# RiskChemi_Sensors_V2_04M2.net
KiCad netlist of a schematic drawn in Altium Designer
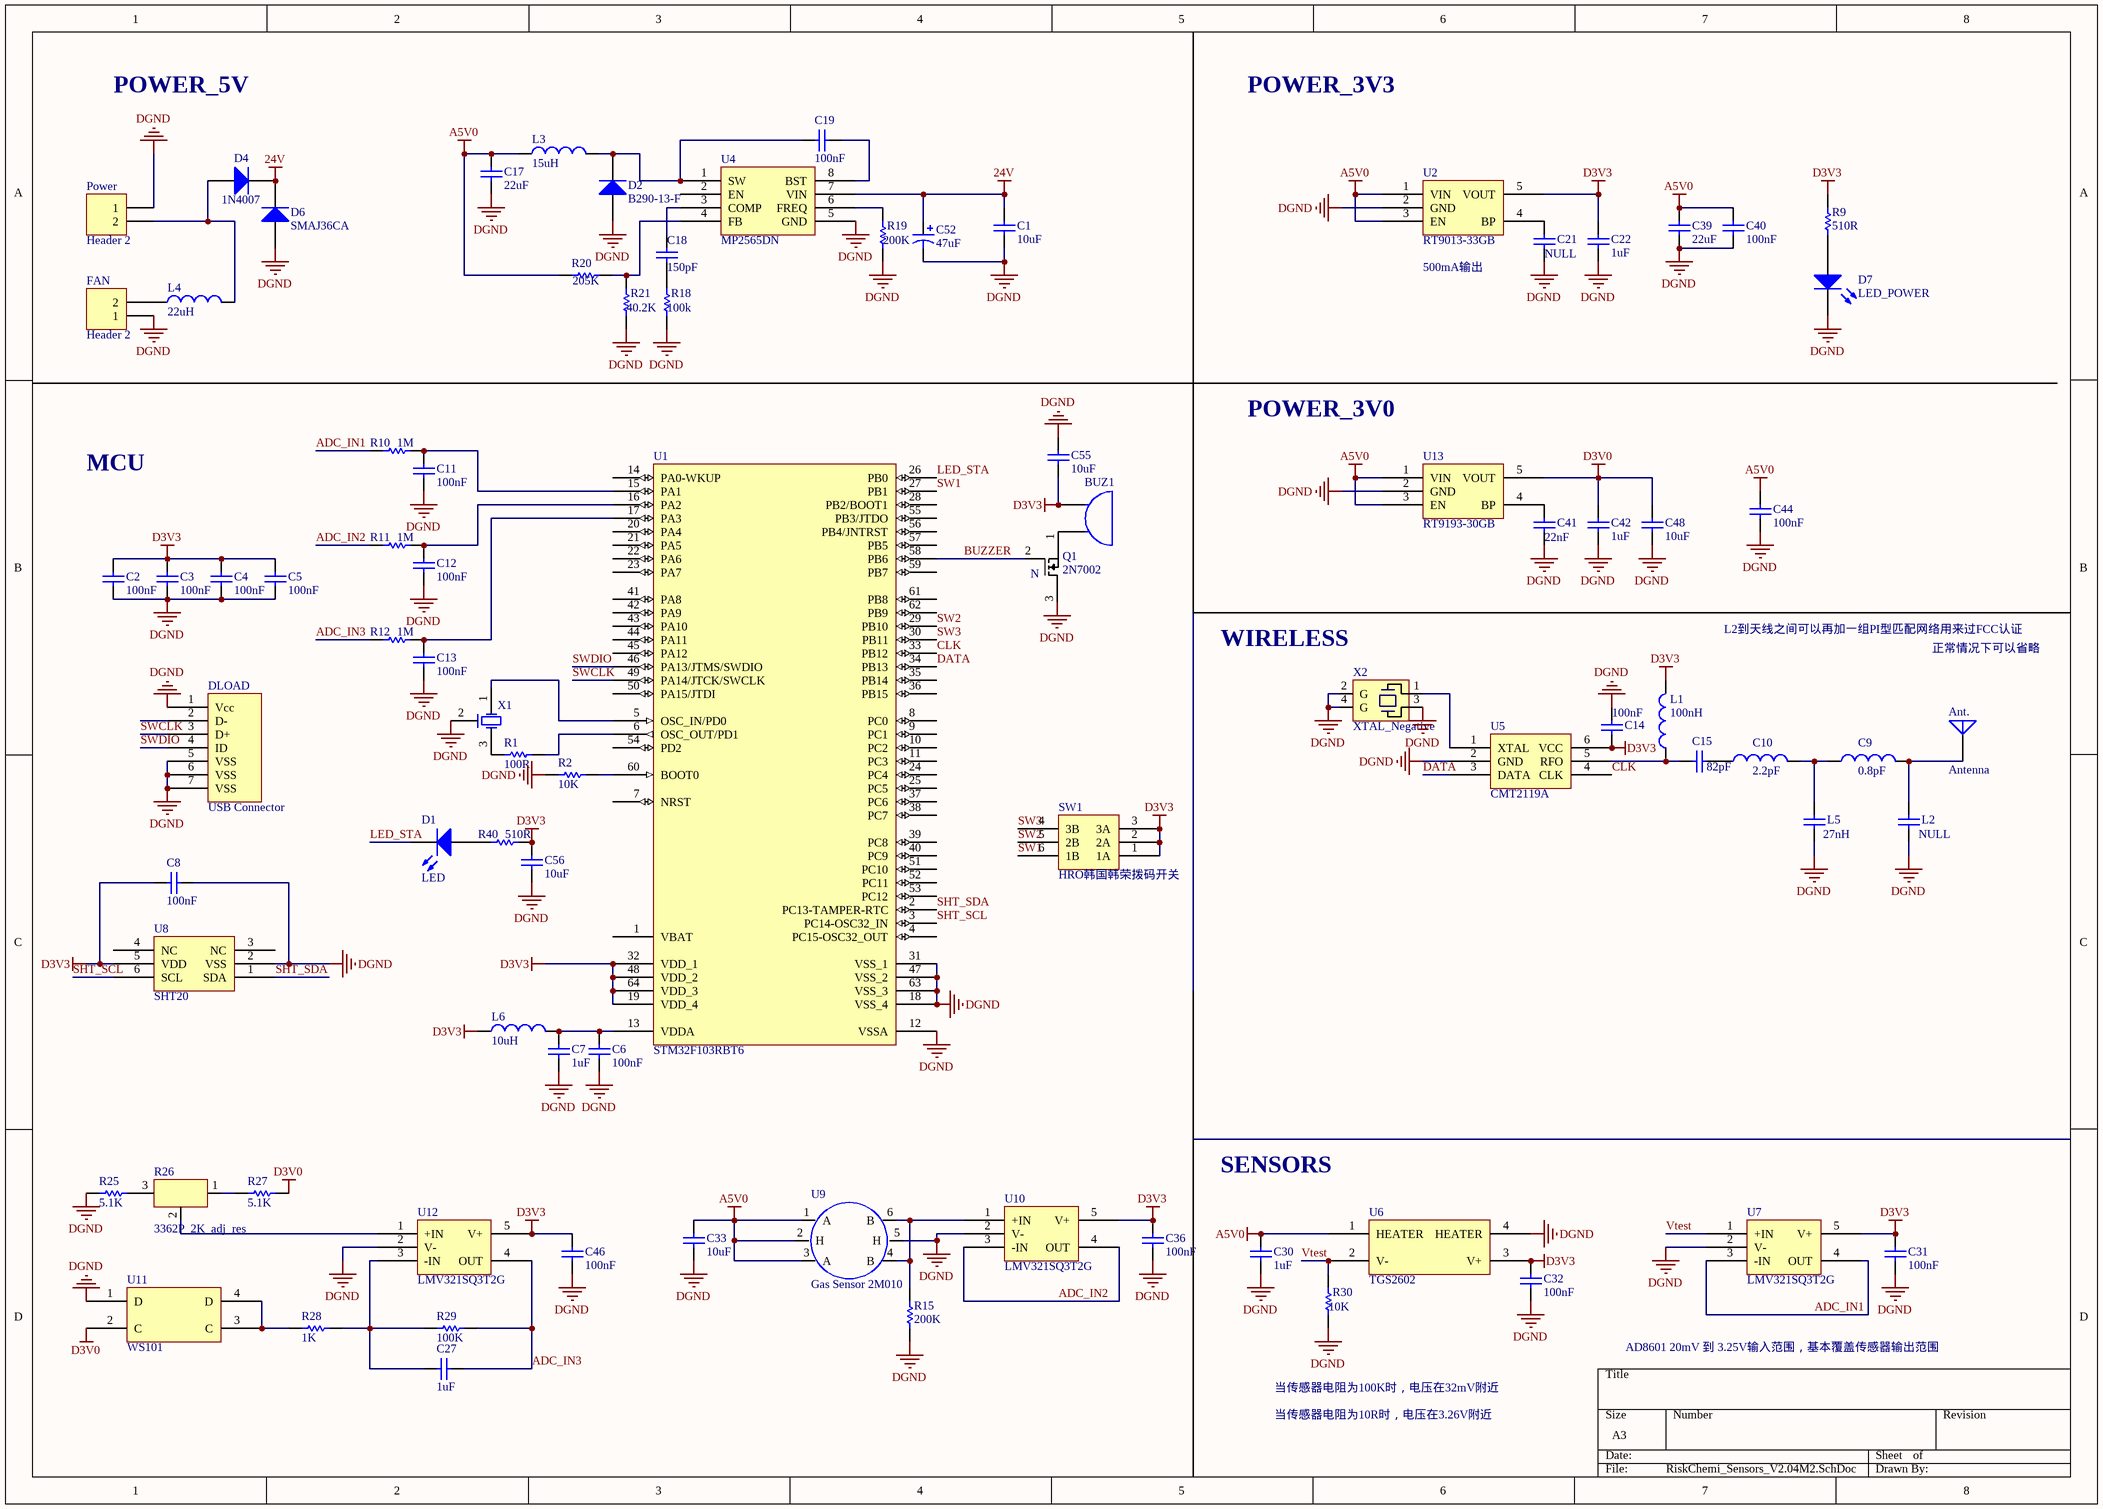
[diagram p0: RiskChemi_Sensors_V2.04M2.SchDoc]

(export (version "E")
  (design (tool "Eeschema 10.0.6"))
  (components
    (comp (ref "Ant.")
      (value "Antenna")
      (footprint "PIN1")
      (description "Generic Antenna")
      (fields (field (name "PUBLISHER") "Altium Limited"))
      (libsource (lib "Miscellaneous Devices") (part "Antenna"))
    )
    (comp (ref "BUZ1")
      (value "BUZZER 0905 through hole")
      (footprint "BUZ0905")
      (description "Buzzer")
      (libsource (lib "杂元件库") (part "BUZZER"))
    )
    (comp (ref "C1")
      (value "10uF")
      (footprint "0805")
      (description "Capacitor,50V")
      (fields (field (name "PUBLISHER") "Altium Limited"))
      (libsource (lib "Miscellaneous Devices") (part "Cap"))
    )
    (comp (ref "C2")
      (value "100nF")
      (footprint "BinFeng:0603")
      (description "Capacitor")
      (fields (field (name "PUBLISHER") "Altium Limited"))
      (libsource (lib "Miscellaneous Devices") (part "Cap"))
    )
    (comp (ref "C3")
      (value "100nF")
      (footprint "BinFeng:0603")
      (description "Capacitor")
      (fields (field (name "PUBLISHER") "Altium Limited"))
      (libsource (lib "Miscellaneous Devices") (part "Cap"))
    )
    (comp (ref "C4")
      (value "100nF")
      (footprint "BinFeng:0603")
      (description "Capacitor")
      (fields (field (name "PUBLISHER") "Altium Limited"))
      (libsource (lib "Miscellaneous Devices") (part "Cap"))
    )
    (comp (ref "C5")
      (value "100nF")
      (footprint "BinFeng:0603")
      (description "Capacitor")
      (fields (field (name "PUBLISHER") "Altium Limited"))
      (libsource (lib "Miscellaneous Devices") (part "Cap"))
    )
    (comp (ref "C6")
      (value "100nF")
      (footprint "BinFeng:0603")
      (description "Capacitor")
      (fields (field (name "PUBLISHER") "Altium Limited"))
      (libsource (lib "Miscellaneous Devices") (part "Cap"))
    )
    (comp (ref "C7")
      (value "1uF")
      (footprint "BinFeng:0603")
      (description "Capacitor")
      (fields (field (name "PUBLISHER") "Altium Limited"))
      (libsource (lib "Miscellaneous Devices") (part "Cap"))
    )
    (comp (ref "C8")
      (value "100nF")
      (footprint "BinFeng:0603")
      (description "Capacitor")
      (fields (field (name "PUBLISHER") "Altium Limited"))
      (libsource (lib "Miscellaneous Devices") (part "Cap"))
    )
    (comp (ref "C9")
      (value "0.8pF")
      (footprint "0603C")
      (description "Inductor")
      (fields (field (name "PUBLISHER") "Altium Limited"))
      (libsource (lib "Miscellaneous Devices") (part "Inductor"))
    )
    (comp (ref "C10")
      (value "2.2pF")
      (footprint "0603C")
      (description "Inductor")
      (fields (field (name "PUBLISHER") "Altium Limited"))
      (libsource (lib "Miscellaneous Devices") (part "Inductor"))
    )
    (comp (ref "C11")
      (value "100nF")
      (footprint "BinFeng:0603")
      (description "Capacitor")
      (fields (field (name "PUBLISHER") "Altium Limited"))
      (libsource (lib "Miscellaneous Devices") (part "Cap"))
    )
    (comp (ref "C12")
      (value "100nF")
      (footprint "BinFeng:0603")
      (description "Capacitor")
      (fields (field (name "PUBLISHER") "Altium Limited"))
      (libsource (lib "Miscellaneous Devices") (part "Cap"))
    )
    (comp (ref "C13")
      (value "100nF")
      (footprint "BinFeng:0603")
      (description "Capacitor")
      (fields (field (name "PUBLISHER") "Altium Limited"))
      (libsource (lib "Miscellaneous Devices") (part "Cap"))
    )
    (comp (ref "C14")
      (value "100nF")
      (footprint "BinFeng:0402")
      (description "Capacitor")
      (fields (field (name "PUBLISHER") "Altium Limited"))
      (libsource (lib "Miscellaneous Devices") (part "Cap"))
    )
    (comp (ref "C15")
      (value "82pF")
      (footprint "BinFeng:0402")
      (description "Capacitor")
      (fields (field (name "PUBLISHER") "Altium Limited"))
      (libsource (lib "Miscellaneous Devices") (part "Cap"))
    )
    (comp (ref "C17")
      (value "22uF")
      (footprint "0805")
      (description "Capacitor,50V")
      (fields (field (name "PUBLISHER") "Altium Limited"))
      (libsource (lib "Miscellaneous Devices") (part "Cap"))
    )
    (comp (ref "C18")
      (value "150pF")
      (footprint "BinFeng:0603")
      (description "Capacitor")
      (fields (field (name "PUBLISHER") "Altium Limited"))
      (libsource (lib "Miscellaneous Devices") (part "Cap"))
    )
    (comp (ref "C19")
      (value "100nF")
      (footprint "BinFeng:0603")
      (description "Capacitor")
      (fields (field (name "PUBLISHER") "Altium Limited"))
      (libsource (lib "Miscellaneous Devices") (part "Cap"))
    )
    (comp (ref "C21")
      (value "NULL")
      (footprint "BinFeng:0402")
      (description "Capacitor")
      (fields (field (name "PUBLISHER") "Altium Limited"))
      (libsource (lib "Miscellaneous Devices") (part "Cap"))
    )
    (comp (ref "C22")
      (value "1uF")
      (footprint "BinFeng:0402")
      (description "Capacitor")
      (fields (field (name "PUBLISHER") "Altium Limited"))
      (libsource (lib "Miscellaneous Devices") (part "Cap"))
    )
    (comp (ref "C27")
      (value "1uF")
      (footprint "BinFeng:0603")
      (description "Capacitor")
      (fields (field (name "PUBLISHER") "Altium Limited"))
      (libsource (lib "Miscellaneous Devices") (part "Cap"))
    )
    (comp (ref "C30")
      (value "1uF")
      (footprint "BinFeng:0603")
      (description "Capacitor")
      (fields (field (name "PUBLISHER") "Altium Limited"))
      (libsource (lib "Miscellaneous Devices") (part "Cap"))
    )
    (comp (ref "C31")
      (value "100nF")
      (footprint "BinFeng:0603")
      (description "Capacitor")
      (fields (field (name "PUBLISHER") "Altium Limited"))
      (libsource (lib "Miscellaneous Devices") (part "Cap"))
    )
    (comp (ref "C32")
      (value "100nF")
      (footprint "BinFeng:0603")
      (description "Capacitor")
      (fields (field (name "PUBLISHER") "Altium Limited"))
      (libsource (lib "Miscellaneous Devices") (part "Cap"))
    )
    (comp (ref "C33")
      (value "10uF")
      (footprint "0805")
      (description "Capacitor")
      (fields (field (name "PUBLISHER") "Altium Limited"))
      (libsource (lib "Miscellaneous Devices") (part "Cap"))
    )
    (comp (ref "C36")
      (value "100nF")
      (footprint "BinFeng:0603")
      (description "Capacitor")
      (fields (field (name "PUBLISHER") "Altium Limited"))
      (libsource (lib "Miscellaneous Devices") (part "Cap"))
    )
    (comp (ref "C39")
      (value "22uF")
      (footprint "1206")
      (description "Capacitor")
      (fields (field (name "PUBLISHER") "Altium Limited"))
      (libsource (lib "Miscellaneous Devices") (part "Cap"))
    )
    (comp (ref "C40")
      (value "100nF")
      (footprint "BinFeng:0402")
      (description "Capacitor")
      (fields (field (name "PUBLISHER") "Altium Limited"))
      (libsource (lib "Miscellaneous Devices") (part "Cap"))
    )
    (comp (ref "C41")
      (value "22nF")
      (footprint "BinFeng:0402")
      (description "Capacitor")
      (fields (field (name "PUBLISHER") "Altium Limited"))
      (libsource (lib "Miscellaneous Devices") (part "Cap"))
    )
    (comp (ref "C42")
      (value "1uF")
      (footprint "BinFeng:0402")
      (description "Capacitor")
      (fields (field (name "PUBLISHER") "Altium Limited"))
      (libsource (lib "Miscellaneous Devices") (part "Cap"))
    )
    (comp (ref "C44")
      (value "100nF")
      (footprint "BinFeng:0402")
      (description "Capacitor")
      (fields (field (name "PUBLISHER") "Altium Limited"))
      (libsource (lib "Miscellaneous Devices") (part "Cap"))
    )
    (comp (ref "C46")
      (value "100nF")
      (footprint "BinFeng:0603")
      (description "Capacitor")
      (fields (field (name "PUBLISHER") "Altium Limited"))
      (libsource (lib "Miscellaneous Devices") (part "Cap"))
    )
    (comp (ref "C48")
      (value "10uF")
      (footprint "0805")
      (description "Capacitor")
      (fields (field (name "PUBLISHER") "Altium Limited"))
      (libsource (lib "Miscellaneous Devices") (part "Cap"))
    )
    (comp (ref "C52")
      (value "47uF")
      (footprint "cap_pol_8*10.2")
      (description "Polarized Capacitor (Radial)")
      (fields (field (name "PUBLISHER") "Altium Limited"))
      (libsource (lib "Miscellaneous Devices") (part "Cap Pol1"))
    )
    (comp (ref "C55")
      (value "10uF")
      (footprint "0805")
      (description "Capacitor")
      (fields (field (name "PUBLISHER") "Altium Limited"))
      (libsource (lib "Miscellaneous Devices") (part "Cap"))
    )
    (comp (ref "C56")
      (value "10uF")
      (footprint "0805")
      (description "Capacitor")
      (fields (field (name "PUBLISHER") "Altium Limited"))
      (libsource (lib "Miscellaneous Devices") (part "Cap"))
    )
    (comp (ref "D1")
      (value "LED")
      (footprint "1206_LED")
      (description "Typical INFRARED GaAs LED")
      (fields (field (name "PUBLISHER") "Altium Limited"))
      (libsource (lib "Miscellaneous Devices") (part "LED0"))
    )
    (comp (ref "D2")
      (value "B290-13-F")
      (footprint "B290")
      (description "Default Diode")
      (fields (field (name "PUBLISHER") "Altium Limited"))
      (libsource (lib "Miscellaneous Devices") (part "Diode"))
    )
    (comp (ref "D4")
      (value "1N4007")
      (footprint "6032_pol")
      (description "1 Amp General Purpose Rectifier")
      (fields (field (name "PUBLISHER") "Altium Limited"))
      (libsource (lib "Miscellaneous Devices") (part "Diode 1N4007"))
    )
    (comp (ref "D6")
      (value "SMAJ36CA")
      (footprint "B290")
      (description "1 Amp General Purpose Rectifier")
      (fields (field (name "PUBLISHER") "Altium Limited"))
      (libsource (lib "Miscellaneous Devices") (part "Diode 1N4007"))
    )
    (comp (ref "D7")
      (value "LED_POWER")
      (footprint "1206_LED")
      (description "Typical INFRARED GaAs LED")
      (fields (field (name "PUBLISHER") "Altium Limited"))
      (libsource (lib "Miscellaneous Devices") (part "LED0"))
    )
    (comp (ref "DLOAD")
      (value "USB Connector")
      (footprint "Mini_USB")
      (libsource (lib "BinFeng_Connectors") (part "Component_1"))
    )
    (comp (ref "FAN")
      (value "Header 2")
      (footprint "HDR1X2")
      (description "Header, 2-Pin")
      (fields (field (name "PUBLISHER") "Altium Limited"))
      (libsource (lib "Miscellaneous Connectors") (part "Header 2"))
    )
    (comp (ref "L1")
      (value "100nH")
      (footprint "0603C")
      (description "Inductor")
      (fields (field (name "PUBLISHER") "Altium Limited"))
      (libsource (lib "Miscellaneous Devices") (part "Inductor"))
    )
    (comp (ref "L2")
      (value "NULL")
      (footprint "BinFeng:0402")
      (description "Capacitor")
      (fields (field (name "PUBLISHER") "Altium Limited"))
      (libsource (lib "Miscellaneous Devices") (part "Cap"))
    )
    (comp (ref "L3")
      (value "15uH")
      (footprint "4*4 Inductor")
      (description "Inductor, 1A")
      (fields (field (name "PUBLISHER") "Altium Limited"))
      (libsource (lib "Miscellaneous Devices") (part "Inductor"))
    )
    (comp (ref "L4")
      (value "22uH")
      (footprint "10*10Inductor")
      (description "Inductor, 1A")
      (fields (field (name "PUBLISHER") "Altium Limited"))
      (libsource (lib "Miscellaneous Devices") (part "Inductor"))
    )
    (comp (ref "L5")
      (value "27nH")
      (footprint "BinFeng:0402")
      (description "Capacitor")
      (fields (field (name "PUBLISHER") "Altium Limited"))
      (libsource (lib "Miscellaneous Devices") (part "Cap"))
    )
    (comp (ref "L6")
      (value "10uH")
      (footprint "0805")
      (description "Inductor")
      (fields (field (name "PUBLISHER") "Altium Limited"))
      (libsource (lib "Miscellaneous Devices") (part "Inductor"))
    )
    (comp (ref "Power")
      (value "Header 2")
      (footprint "HDR1X2")
      (description "Header, 2-Pin")
      (fields (field (name "PUBLISHER") "Altium Limited"))
      (libsource (lib "") (part "Header 2_1"))
    )
    (comp (ref "Q1") (value "2N7002") (footprint "2N7002") (libsource (lib "seeder") (part "N-MOSFET")))
    (comp (ref "R1")
      (value "100R")
      (footprint "BinFeng:0603")
      (description "Resistor")
      (fields (field (name "PUBLISHER") "Altium Limited"))
      (libsource (lib "Miscellaneous Devices") (part "Res1"))
    )
    (comp (ref "R2")
      (value "10K")
      (footprint "BinFeng:0603")
      (description "Resistor")
      (fields (field (name "PUBLISHER") "Altium Limited"))
      (libsource (lib "Miscellaneous Devices") (part "Res1"))
    )
    (comp (ref "R9")
      (value "510R")
      (footprint "BinFeng:0603")
      (description "Resistor")
      (fields (field (name "PUBLISHER") "Altium Limited"))
      (libsource (lib "Miscellaneous Devices") (part "Res1"))
    )
    (comp (ref "R10")
      (value "1M")
      (footprint "BinFeng:0603")
      (description "Resistor")
      (fields (field (name "PUBLISHER") "Altium Limited"))
      (libsource (lib "Miscellaneous Devices") (part "Res1"))
    )
    (comp (ref "R11")
      (value "1M")
      (footprint "BinFeng:0603")
      (description "Resistor")
      (fields (field (name "PUBLISHER") "Altium Limited"))
      (libsource (lib "Miscellaneous Devices") (part "Res1"))
    )
    (comp (ref "R12")
      (value "1M")
      (footprint "BinFeng:0603")
      (description "Resistor")
      (fields (field (name "PUBLISHER") "Altium Limited"))
      (libsource (lib "Miscellaneous Devices") (part "Res1"))
    )
    (comp (ref "R15")
      (value "200K")
      (footprint "BinFeng:0603C")
      (description "Resistor")
      (fields (field (name "PUBLISHER") "Altium Limited"))
      (libsource (lib "Miscellaneous Devices") (part "Res1"))
    )
    (comp (ref "R18")
      (value "100k")
      (footprint "BinFeng:0603")
      (description "Resistor")
      (fields (field (name "PUBLISHER") "Altium Limited"))
      (libsource (lib "Miscellaneous Devices") (part "Res1"))
    )
    (comp (ref "R19")
      (value "200K")
      (footprint "BinFeng:0402")
      (description "Resistor")
      (fields (field (name "PUBLISHER") "Altium Limited"))
      (libsource (lib "Miscellaneous Devices") (part "Res1"))
    )
    (comp (ref "R20")
      (value "205K")
      (footprint "BinFeng:0603")
      (description "Resistor")
      (fields (field (name "PUBLISHER") "Altium Limited"))
      (libsource (lib "Miscellaneous Devices") (part "Res1"))
    )
    (comp (ref "R21")
      (value "40.2K")
      (footprint "BinFeng:0603")
      (description "Resistor")
      (fields (field (name "PUBLISHER") "Altium Limited"))
      (libsource (lib "Miscellaneous Devices") (part "Res1"))
    )
    (comp (ref "R25")
      (value "5.1K")
      (footprint "BinFeng:0603")
      (description "Resistor")
      (fields (field (name "PUBLISHER") "Altium Limited"))
      (libsource (lib "Miscellaneous Devices") (part "Res1"))
    )
    (comp (ref "R26")
      (value "3362P_2K_adj_res")
      (footprint "res_adj")
      (libsource (lib "BinFeng_IC") (part "res_adj"))
    )
    (comp (ref "R27")
      (value "5.1K")
      (footprint "BinFeng:0603")
      (description "Resistor")
      (fields (field (name "PUBLISHER") "Altium Limited"))
      (libsource (lib "Miscellaneous Devices") (part "Res1"))
    )
    (comp (ref "R28")
      (value "1K")
      (footprint "BinFeng:0603")
      (description "Resistor")
      (fields (field (name "PUBLISHER") "Altium Limited"))
      (libsource (lib "Miscellaneous Devices") (part "Res1"))
    )
    (comp (ref "R29")
      (value "100K")
      (footprint "BinFeng:0603")
      (description "Resistor")
      (fields (field (name "PUBLISHER") "Altium Limited"))
      (libsource (lib "Miscellaneous Devices") (part "Res1"))
    )
    (comp (ref "R30")
      (value "10K")
      (footprint "BinFeng:0603")
      (description "Resistor")
      (fields (field (name "PUBLISHER") "Altium Limited"))
      (libsource (lib "Miscellaneous Devices") (part "Res1"))
    )
    (comp (ref "R40")
      (value "510R")
      (footprint "BinFeng:0603")
      (description "Resistor")
      (fields (field (name "PUBLISHER") "Altium Limited"))
      (libsource (lib "Miscellaneous Devices") (part "Res1"))
    )
    (comp (ref "SW1")
      (value "HRO韩国韩荣拨码开关")
      (footprint "SW_6P_HRO")
      (libsource (lib "BinFeng_IC") (part "SW_6P"))
    )
    (comp (ref "U1")
      (value "STM32F103RBT6")
      (footprint "LQFP64_N")
      (description "STM32 ARM-based 32-bit MCU with 64 Kbytes Flash, 64-pin LQFP, Industrial Temperature")
      (fields (field (name "PUBLISHER") "Altium Limited"))
      (libsource (lib "ST Microcontroller 32-Bit STM32") (part "STM32F103R8T6"))
    )
    (comp (ref "U2")
      (value "RT9013-33GB")
      (footprint "SOT-23-5")
      (libsource (lib "BinFeng_IC") (part "RT9193"))
    )
    (comp (ref "U4")
      (value "MP2565DN")
      (footprint "so-8")
      (description "DCDC 4.5V~28V input 1.8V ~5V output low power")
      (libsource (lib "BinFeng_IC") (part "MP1584"))
    )
    (comp (ref "U5")
      (value "CMT2119A")
      (footprint "sot23-6")
      (libsource (lib "BinFeng_IC") (part "CMT2119A"))
    )
    (comp (ref "U6")
      (value "TGS2602")
      (footprint "Gas Sensor TGS2602 Slot")
      (description "VOC sensor")
      (libsource (lib "BinFeng_IC") (part "TGS2602"))
    )
    (comp (ref "U7")
      (value "LMV321SQ3T2G")
      (footprint "SC-70-5")
      (libsource (lib "BinFeng_IC") (part "LMV321SQ3T2G"))
    )
    (comp (ref "U8") (value "SHT20") (footprint "SHT20") (libsource (lib "BinFeng_IC") (part "SHT20")))
    (comp (ref "U9")
      (value "Gas Sensor 2M010")
      (footprint "Gas Sensor 2M010 Slot")
      (libsource (lib "BinFeng_IC") (part "Gas Sensor"))
    )
    (comp (ref "U10")
      (value "LMV321SQ3T2G")
      (footprint "SC-70-5")
      (libsource (lib "BinFeng_IC") (part "LMV321SQ3T2G"))
    )
    (comp (ref "U11")
      (value "WS101")
      (footprint "Gas_Sensor_WS101_Slot")
      (libsource (lib "BinFeng_IC") (part "Gas Sensor_WS101"))
    )
    (comp (ref "U12")
      (value "LMV321SQ3T2G")
      (footprint "SC-70-5")
      (libsource (lib "BinFeng_IC") (part "LMV321SQ3T2G"))
    )
    (comp (ref "U13")
      (value "RT9193-30GB")
      (footprint "SOT-23-5")
      (libsource (lib "BinFeng_IC") (part "RT9193"))
    )
    (comp (ref "X1") (value "8M smd") (footprint "8Mhz_XTAL") (libsource (lib "Schlib1") (part "8M smd")))
    (comp (ref "X2")
      (value "XTAL_Negative")
      (footprint "XTAL3225")
      (libsource (lib "BinFeng_IC") (part "XTAL_Negative"))
    )
  )
  (nets
    (net (code "1") (name "/ADC_IN1") (class "Default")
      (node (ref "R10") (pin "1") (pinfunction "1_1") (pintype "passive"))
      (node (ref "U7") (pin "3") (pinfunction "-IN_3") (pintype "passive"))
      (node (ref "U7") (pin "4") (pinfunction "OUT_4") (pintype "passive"))
    )
    (net (code "2") (name "/ADC_IN2") (class "Default")
      (node (ref "R11") (pin "1") (pinfunction "1_1") (pintype "passive"))
      (node (ref "U10") (pin "3") (pinfunction "-IN_3") (pintype "passive"))
      (node (ref "U10") (pin "4") (pinfunction "OUT_4") (pintype "passive"))
    )
    (net (code "3") (name "/ADC_IN3") (class "Default")
      (node (ref "C27") (pin "1") (pinfunction "1_1") (pintype "passive"))
      (node (ref "R12") (pin "1") (pinfunction "1_1") (pintype "passive"))
      (node (ref "R29") (pin "2") (pinfunction "2_2") (pintype "passive"))
      (node (ref "U12") (pin "4") (pinfunction "OUT_4") (pintype "passive"))
    )
    (net (code "4") (name "/BUZZER") (class "Default")
      (node (ref "Q1") (pin "2") (pinfunction "G_2") (pintype "passive"))
      (node (ref "U1") (pin "58") (pinfunction "PB6_58") (pintype "bidirectional"))
    )
    (net (code "5") (name "/CLK") (class "Default")
      (node (ref "U1") (pin "33") (pinfunction "PB12_33") (pintype "bidirectional"))
      (node (ref "U5") (pin "4") (pinfunction "CLK_4") (pintype "passive"))
    )
    (net (code "6") (name "/DATA") (class "Default")
      (node (ref "U1") (pin "34") (pinfunction "PB13_34") (pintype "bidirectional"))
      (node (ref "U5") (pin "3") (pinfunction "DATA_3") (pintype "passive"))
    )
    (net (code "7") (name "/LED_STA") (class "Default")
      (node (ref "D1") (pin "2") (pinfunction "K_2") (pintype "passive"))
      (node (ref "U1") (pin "26") (pinfunction "PB0_26") (pintype "bidirectional"))
    )
    (net (code "8") (name "/SHT_SCL") (class "Default")
      (node (ref "U1") (pin "3") (pinfunction "PC14-OSC32_IN_3") (pintype "bidirectional"))
      (node (ref "U8") (pin "6") (pinfunction "SCL_6") (pintype "passive"))
    )
    (net (code "9") (name "/SHT_SDA") (class "Default")
      (node (ref "U1") (pin "2") (pinfunction "PC13-TAMPER-RTC_2") (pintype "bidirectional"))
      (node (ref "U8") (pin "1") (pinfunction "SDA_1") (pintype "passive"))
    )
    (net (code "10") (name "/SW1") (class "Default")
      (node (ref "SW1") (pin "6") (pinfunction "1B_6") (pintype "passive"))
      (node (ref "U1") (pin "27") (pinfunction "PB1_27") (pintype "bidirectional"))
    )
    (net (code "11") (name "/SW2") (class "Default")
      (node (ref "SW1") (pin "5") (pinfunction "2B_5") (pintype "passive"))
      (node (ref "U1") (pin "29") (pinfunction "PB10_29") (pintype "bidirectional"))
    )
    (net (code "12") (name "/SW3") (class "Default")
      (node (ref "SW1") (pin "4") (pinfunction "3B_4") (pintype "passive"))
      (node (ref "U1") (pin "30") (pinfunction "PB11_30") (pintype "bidirectional"))
    )
    (net (code "13") (name "/SWCLK") (class "Default")
      (node (ref "DLOAD") (pin "3") (pinfunction "D+_3") (pintype "passive"))
      (node (ref "U1") (pin "49") (pinfunction "PA14/JTCK/SWCLK_49") (pintype "bidirectional"))
    )
    (net (code "14") (name "/SWDIO") (class "Default")
      (node (ref "DLOAD") (pin "4") (pinfunction "ID_4") (pintype "passive"))
      (node (ref "U1") (pin "46") (pinfunction "PA13/JTMS/SWDIO_46") (pintype "bidirectional"))
    )
    (net (code "15") (name "/Vtest") (class "Default")
      (node (ref "R30") (pin "2") (pinfunction "2_2") (pintype "passive"))
      (node (ref "U6") (pin "2") (pinfunction "V-_2") (pintype "passive"))
      (node (ref "U7") (pin "1") (pinfunction "+IN_1") (pintype "passive"))
    )
    (net (code "16") (name "24V") (class "Default")
      (node (ref "C1") (pin "2") (pinfunction "2_2") (pintype "passive"))
      (node (ref "C52") (pin "1") (pinfunction "1_1") (pintype "passive"))
      (node (ref "D4") (pin "2") (pinfunction "K_2") (pintype "passive"))
      (node (ref "D6") (pin "2") (pinfunction "K_2") (pintype "passive"))
      (node (ref "U4") (pin "7") (pinfunction "VIN_7") (pintype "passive"))
    )
    (net (code "17") (name "A5V0") (class "Default")
      (node (ref "C17") (pin "2") (pinfunction "2_2") (pintype "passive"))
      (node (ref "C30") (pin "2") (pinfunction "2_2") (pintype "passive"))
      (node (ref "C33") (pin "2") (pinfunction "2_2") (pintype "passive"))
      (node (ref "C39") (pin "1") (pinfunction "1_1") (pintype "passive"))
      (node (ref "C40") (pin "2") (pinfunction "2_2") (pintype "passive"))
      (node (ref "C44") (pin "2") (pinfunction "2_2") (pintype "passive"))
      (node (ref "L3") (pin "1") (pinfunction "1_1") (pintype "passive"))
      (node (ref "R20") (pin "2") (pinfunction "2_2") (pintype "passive"))
      (node (ref "U13") (pin "1") (pinfunction "VIN_1") (pintype "passive"))
      (node (ref "U13") (pin "3") (pinfunction "EN_3") (pintype "passive"))
      (node (ref "U2") (pin "1") (pinfunction "VIN_1") (pintype "passive"))
      (node (ref "U2") (pin "3") (pinfunction "EN_3") (pintype "passive"))
      (node (ref "U6") (pin "1") (pinfunction "HEATER_1") (pintype "passive"))
      (node (ref "U9") (pin "1") (pinfunction "A_1") (pintype "passive"))
      (node (ref "U9") (pin "2") (pinfunction "H_2") (pintype "passive"))
      (node (ref "U9") (pin "3") (pinfunction "A_3") (pintype "passive"))
    )
    (net (code "18") (name "D3V0") (class "Default")
      (node (ref "C42") (pin "2") (pinfunction "2_2") (pintype "passive"))
      (node (ref "C48") (pin "2") (pinfunction "2_2") (pintype "passive"))
      (node (ref "R27") (pin "2") (pinfunction "2_2") (pintype "passive"))
      (node (ref "U11") (pin "2") (pinfunction "C_2") (pintype "passive"))
      (node (ref "U13") (pin "5") (pinfunction "VOUT_5") (pintype "passive"))
    )
    (net (code "19") (name "D3V3") (class "Default")
      (node (ref "BUZ1") (pin "1") (pinfunction "A_1") (pintype "passive"))
      (node (ref "C14") (pin "2") (pinfunction "2_2") (pintype "passive"))
      (node (ref "C2") (pin "2") (pinfunction "2_2") (pintype "passive"))
      (node (ref "C22") (pin "2") (pinfunction "2_2") (pintype "passive"))
      (node (ref "C3") (pin "2") (pinfunction "2_2") (pintype "passive"))
      (node (ref "C31") (pin "2") (pinfunction "2_2") (pintype "passive"))
      (node (ref "C32") (pin "2") (pinfunction "2_2") (pintype "passive"))
      (node (ref "C36") (pin "2") (pinfunction "2_2") (pintype "passive"))
      (node (ref "C4") (pin "2") (pinfunction "2_2") (pintype "passive"))
      (node (ref "C46") (pin "2") (pinfunction "2_2") (pintype "passive"))
      (node (ref "C5") (pin "2") (pinfunction "2_2") (pintype "passive"))
      (node (ref "C55") (pin "2") (pinfunction "2_2") (pintype "passive"))
      (node (ref "C56") (pin "2") (pinfunction "2_2") (pintype "passive"))
      (node (ref "C8") (pin "2") (pinfunction "2_2") (pintype "passive"))
      (node (ref "L1") (pin "2") (pinfunction "2_2") (pintype "passive"))
      (node (ref "L6") (pin "1") (pinfunction "1_1") (pintype "passive"))
      (node (ref "R40") (pin "2") (pinfunction "2_2") (pintype "passive"))
      (node (ref "R9") (pin "2") (pinfunction "2_2") (pintype "passive"))
      (node (ref "SW1") (pin "1") (pinfunction "1A_1") (pintype "passive"))
      (node (ref "SW1") (pin "2") (pinfunction "2A_2") (pintype "passive"))
      (node (ref "SW1") (pin "3") (pinfunction "3A_3") (pintype "passive"))
      (node (ref "U1") (pin "19") (pinfunction "VDD_4_19") (pintype "power_in"))
      (node (ref "U1") (pin "32") (pinfunction "VDD_1_32") (pintype "power_in"))
      (node (ref "U1") (pin "48") (pinfunction "VDD_2_48") (pintype "power_in"))
      (node (ref "U1") (pin "64") (pinfunction "VDD_3_64") (pintype "power_in"))
      (node (ref "U10") (pin "5") (pinfunction "V+_5") (pintype "passive"))
      (node (ref "U12") (pin "5") (pinfunction "V+_5") (pintype "passive"))
      (node (ref "U2") (pin "5") (pinfunction "VOUT_5") (pintype "passive"))
      (node (ref "U5") (pin "6") (pinfunction "VCC_6") (pintype "passive"))
      (node (ref "U6") (pin "3") (pinfunction "V+_3") (pintype "passive"))
      (node (ref "U7") (pin "5") (pinfunction "V+_5") (pintype "passive"))
      (node (ref "U8") (pin "5") (pinfunction "VDD_5") (pintype "passive"))
    )
    (net (code "20") (name "DGND") (class "Default")
      (node (ref "C1") (pin "1") (pinfunction "1_1") (pintype "passive"))
      (node (ref "C11") (pin "2") (pinfunction "2_2") (pintype "passive"))
      (node (ref "C12") (pin "1") (pinfunction "1_1") (pintype "passive"))
      (node (ref "C13") (pin "1") (pinfunction "1_1") (pintype "passive"))
      (node (ref "C14") (pin "1") (pinfunction "1_1") (pintype "passive"))
      (node (ref "C17") (pin "1") (pinfunction "1_1") (pintype "passive"))
      (node (ref "C2") (pin "1") (pinfunction "1_1") (pintype "passive"))
      (node (ref "C21") (pin "1") (pinfunction "1_1") (pintype "passive"))
      (node (ref "C22") (pin "1") (pinfunction "1_1") (pintype "passive"))
      (node (ref "C3") (pin "1") (pinfunction "1_1") (pintype "passive"))
      (node (ref "C30") (pin "1") (pinfunction "1_1") (pintype "passive"))
      (node (ref "C31") (pin "1") (pinfunction "1_1") (pintype "passive"))
      (node (ref "C32") (pin "1") (pinfunction "1_1") (pintype "passive"))
      (node (ref "C33") (pin "1") (pinfunction "1_1") (pintype "passive"))
      (node (ref "C36") (pin "1") (pinfunction "1_1") (pintype "passive"))
      (node (ref "C39") (pin "2") (pinfunction "2_2") (pintype "passive"))
      (node (ref "C4") (pin "1") (pinfunction "1_1") (pintype "passive"))
      (node (ref "C40") (pin "1") (pinfunction "1_1") (pintype "passive"))
      (node (ref "C41") (pin "1") (pinfunction "1_1") (pintype "passive"))
      (node (ref "C42") (pin "1") (pinfunction "1_1") (pintype "passive"))
      (node (ref "C44") (pin "1") (pinfunction "1_1") (pintype "passive"))
      (node (ref "C46") (pin "1") (pinfunction "1_1") (pintype "passive"))
      (node (ref "C48") (pin "1") (pinfunction "1_1") (pintype "passive"))
      (node (ref "C5") (pin "1") (pinfunction "1_1") (pintype "passive"))
      (node (ref "C52") (pin "2") (pinfunction "2_2") (pintype "passive"))
      (node (ref "C55") (pin "1") (pinfunction "1_1") (pintype "passive"))
      (node (ref "C56") (pin "1") (pinfunction "1_1") (pintype "passive"))
      (node (ref "C6") (pin "1") (pinfunction "1_1") (pintype "passive"))
      (node (ref "C7") (pin "1") (pinfunction "1_1") (pintype "passive"))
      (node (ref "C8") (pin "1") (pinfunction "1_1") (pintype "passive"))
      (node (ref "D2") (pin "1") (pinfunction "A_1") (pintype "passive"))
      (node (ref "D6") (pin "1") (pinfunction "A_1") (pintype "passive"))
      (node (ref "D7") (pin "2") (pinfunction "K_2") (pintype "passive"))
      (node (ref "DLOAD") (pin "1") (pinfunction "Vcc_1") (pintype "passive"))
      (node (ref "DLOAD") (pin "5") (pinfunction "VSS_5") (pintype "passive"))
      (node (ref "DLOAD") (pin "6") (pinfunction "VSS_6") (pintype "passive"))
      (node (ref "DLOAD") (pin "7") (pinfunction "VSS_7") (pintype "passive"))
      (node (ref "FAN") (pin "1") (pinfunction "1_1") (pintype "passive"))
      (node (ref "L2") (pin "1") (pinfunction "1_1") (pintype "passive"))
      (node (ref "L5") (pin "1") (pinfunction "1_1") (pintype "passive"))
      (node (ref "Power") (pin "1") (pinfunction "1_1") (pintype "passive"))
      (node (ref "Q1") (pin "3") (pinfunction "S_3") (pintype "passive"))
      (node (ref "R15") (pin "2") (pinfunction "2_2") (pintype "passive"))
      (node (ref "R18") (pin "1") (pinfunction "1_1") (pintype "passive"))
      (node (ref "R19") (pin "1") (pinfunction "1_1") (pintype "passive"))
      (node (ref "R2") (pin "1") (pinfunction "1_1") (pintype "passive"))
      (node (ref "R21") (pin "1") (pinfunction "1_1") (pintype "passive"))
      (node (ref "R25") (pin "1") (pinfunction "1_1") (pintype "passive"))
      (node (ref "R30") (pin "1") (pinfunction "1_1") (pintype "passive"))
      (node (ref "U1") (pin "12") (pinfunction "VSSA_12") (pintype "power_in"))
      (node (ref "U1") (pin "18") (pinfunction "VSS_4_18") (pintype "power_in"))
      (node (ref "U1") (pin "31") (pinfunction "VSS_1_31") (pintype "power_in"))
      (node (ref "U1") (pin "47") (pinfunction "VSS_2_47") (pintype "power_in"))
      (node (ref "U1") (pin "63") (pinfunction "VSS_3_63") (pintype "power_in"))
      (node (ref "U10") (pin "2") (pinfunction "V-_2") (pintype "passive"))
      (node (ref "U11") (pin "1") (pinfunction "D_1") (pintype "passive"))
      (node (ref "U12") (pin "2") (pinfunction "V-_2") (pintype "passive"))
      (node (ref "U13") (pin "2") (pinfunction "GND_2") (pintype "passive"))
      (node (ref "U2") (pin "2") (pinfunction "GND_2") (pintype "passive"))
      (node (ref "U4") (pin "5") (pinfunction "GND_5") (pintype "passive"))
      (node (ref "U5") (pin "2") (pinfunction "GND_2") (pintype "passive"))
      (node (ref "U6") (pin "4") (pinfunction "HEATER_4") (pintype "passive"))
      (node (ref "U7") (pin "2") (pinfunction "V-_2") (pintype "passive"))
      (node (ref "U8") (pin "2") (pinfunction "VSS_2") (pintype "passive"))
      (node (ref "U9") (pin "5") (pinfunction "H_5") (pintype "passive"))
      (node (ref "X1") (pin "2") (pinfunction "GND_2") (pintype "passive"))
      (node (ref "X2") (pin "2") (pinfunction "G_2") (pintype "passive"))
      (node (ref "X2") (pin "3") (pintype "passive"))
      (node (ref "X2") (pin "4") (pinfunction "G_4") (pintype "passive"))
    )
    (net (code "21") (name "Net-(Ant.-A)") (class "Default")
      (node (ref "Ant.") (pin "1") (pinfunction "A_1") (pintype "passive"))
      (node (ref "C9") (pin "2") (pinfunction "2_2") (pintype "passive"))
      (node (ref "L2") (pin "2") (pinfunction "2_2") (pintype "passive"))
    )
    (net (code "22") (name "Net-(BUZ1-B)") (class "Default")
      (node (ref "BUZ1") (pin "2") (pinfunction "B_2") (pintype "passive"))
      (node (ref "Q1") (pin "1") (pinfunction "D_1") (pintype "passive"))
    )
    (net (code "23") (name "Net-(C10-Pad1)") (class "Default")
      (node (ref "C10") (pin "1") (pinfunction "1_1") (pintype "passive"))
      (node (ref "C15") (pin "2") (pinfunction "2_2") (pintype "passive"))
    )
    (net (code "24") (name "Net-(C10-Pad2)") (class "Default")
      (node (ref "C10") (pin "2") (pinfunction "2_2") (pintype "passive"))
      (node (ref "C9") (pin "1") (pinfunction "1_1") (pintype "passive"))
      (node (ref "L5") (pin "2") (pinfunction "2_2") (pintype "passive"))
    )
    (net (code "25") (name "Net-(C18-Pad2)") (class "Default")
      (node (ref "C18") (pin "2") (pinfunction "2_2") (pintype "passive"))
      (node (ref "R18") (pin "2") (pinfunction "2_2") (pintype "passive"))
    )
    (net (code "26") (name "Net-(D1-A)") (class "Default")
      (node (ref "D1") (pin "1") (pinfunction "A_1") (pintype "passive"))
      (node (ref "R40") (pin "1") (pinfunction "1_1") (pintype "passive"))
    )
    (net (code "27") (name "Net-(D2-K)") (class "Default")
      (node (ref "C19") (pin "2") (pinfunction "2_2") (pintype "passive"))
      (node (ref "D2") (pin "2") (pinfunction "K_2") (pintype "passive"))
      (node (ref "L3") (pin "2") (pinfunction "2_2") (pintype "passive"))
      (node (ref "U4") (pin "1") (pinfunction "SW_1") (pintype "passive"))
    )
    (net (code "28") (name "Net-(D4-A)") (class "Default")
      (node (ref "D4") (pin "1") (pinfunction "A_1") (pintype "passive"))
      (node (ref "L4") (pin "2") (pinfunction "2_2") (pintype "passive"))
      (node (ref "Power") (pin "2") (pinfunction "2_2") (pintype "passive"))
    )
    (net (code "29") (name "Net-(D7-A)") (class "Default")
      (node (ref "D7") (pin "1") (pinfunction "A_1") (pintype "passive"))
      (node (ref "R9") (pin "1") (pinfunction "1_1") (pintype "passive"))
    )
    (net (code "30") (name "Net-(FAN-Pad2)") (class "Default")
      (node (ref "FAN") (pin "2") (pinfunction "2_2") (pintype "passive"))
      (node (ref "L4") (pin "1") (pinfunction "1_1") (pintype "passive"))
    )
    (net (code "31") (name "Net-(R25-Pad2)") (class "Default")
      (node (ref "R25") (pin "2") (pinfunction "2_2") (pintype "passive"))
      (node (ref "R26") (pin "3") (pintype "passive"))
    )
    (net (code "32") (name "Net-(R26-Pad1)") (class "Default")
      (node (ref "R26") (pin "1") (pintype "passive"))
      (node (ref "R27") (pin "1") (pinfunction "1_1") (pintype "passive"))
    )
    (net (code "33") (name "Net-(R28-Pad1)") (class "Default")
      (node (ref "R28") (pin "1") (pinfunction "1_1") (pintype "passive"))
      (node (ref "U11") (pin "3") (pinfunction "C_3") (pintype "passive"))
      (node (ref "U11") (pin "4") (pinfunction "D_4") (pintype "passive"))
    )
    (net (code "34") (name "Net-(U1-BOOT0)") (class "Default")
      (node (ref "R2") (pin "2") (pinfunction "2_2") (pintype "passive"))
      (node (ref "U1") (pin "60") (pinfunction "BOOT0_60") (pintype "input"))
    )
    (net (code "35") (name "Net-(U1-OSC_IN{slash}PD0)") (class "Default")
      (node (ref "U1") (pin "5") (pinfunction "OSC_IN/PD0_5") (pintype "input"))
      (node (ref "X1") (pin "1") (pinfunction "OSC1_1") (pintype "passive"))
    )
    (net (code "36") (name "Net-(U1-OSC_OUT{slash}PD1)") (class "Default")
      (node (ref "R1") (pin "2") (pinfunction "2_2") (pintype "passive"))
      (node (ref "U1") (pin "6") (pinfunction "OSC_OUT/PD1_6") (pintype "output"))
    )
    (net (code "37") (name "Net-(U1-PA1)") (class "Default")
      (node (ref "C11") (pin "1") (pinfunction "1_1") (pintype "passive"))
      (node (ref "R10") (pin "2") (pinfunction "2_2") (pintype "passive"))
      (node (ref "U1") (pin "15") (pinfunction "PA1_15") (pintype "bidirectional"))
    )
    (net (code "38") (name "Net-(U1-PA2)") (class "Default")
      (node (ref "C12") (pin "2") (pinfunction "2_2") (pintype "passive"))
      (node (ref "R11") (pin "2") (pinfunction "2_2") (pintype "passive"))
      (node (ref "U1") (pin "16") (pinfunction "PA2_16") (pintype "bidirectional"))
    )
    (net (code "39") (name "Net-(U1-PA3)") (class "Default")
      (node (ref "C13") (pin "2") (pinfunction "2_2") (pintype "passive"))
      (node (ref "R12") (pin "2") (pinfunction "2_2") (pintype "passive"))
      (node (ref "U1") (pin "17") (pinfunction "PA3_17") (pintype "bidirectional"))
    )
    (net (code "40") (name "Net-(U1-VDDA)") (class "Default")
      (node (ref "C6") (pin "2") (pinfunction "2_2") (pintype "passive"))
      (node (ref "C7") (pin "2") (pinfunction "2_2") (pintype "passive"))
      (node (ref "L6") (pin "2") (pinfunction "2_2") (pintype "passive"))
      (node (ref "U1") (pin "13") (pinfunction "VDDA_13") (pintype "power_in"))
    )
    (net (code "41") (name "Net-(U2-BP)") (class "Default")
      (node (ref "C21") (pin "2") (pinfunction "2_2") (pintype "passive"))
      (node (ref "U2") (pin "4") (pinfunction "BP_4") (pintype "passive"))
    )
    (net (code "42") (name "Net-(U4-BST)") (class "Default")
      (node (ref "C19") (pin "1") (pinfunction "1_1") (pintype "passive"))
      (node (ref "U4") (pin "8") (pinfunction "BST_8") (pintype "passive"))
    )
    (net (code "43") (name "Net-(U4-COMP)") (class "Default")
      (node (ref "C18") (pin "1") (pinfunction "1_1") (pintype "passive"))
      (node (ref "U4") (pin "3") (pinfunction "COMP_3") (pintype "passive"))
    )
    (net (code "44") (name "Net-(U4-FB)") (class "Default")
      (node (ref "R20") (pin "1") (pinfunction "1_1") (pintype "passive"))
      (node (ref "R21") (pin "2") (pinfunction "2_2") (pintype "passive"))
      (node (ref "U4") (pin "4") (pinfunction "FB_4") (pintype "passive"))
    )
    (net (code "45") (name "Net-(U4-FREQ)") (class "Default")
      (node (ref "R19") (pin "2") (pinfunction "2_2") (pintype "passive"))
      (node (ref "U4") (pin "6") (pinfunction "FREQ_6") (pintype "passive"))
    )
    (net (code "46") (name "Net-(U5-RFO)") (class "Default")
      (node (ref "C15") (pin "1") (pinfunction "1_1") (pintype "passive"))
      (node (ref "L1") (pin "1") (pinfunction "1_1") (pintype "passive"))
      (node (ref "U5") (pin "5") (pinfunction "RFO_5") (pintype "passive"))
    )
    (net (code "47") (name "Net-(U5-XTAL)") (class "Default")
      (node (ref "U5") (pin "1") (pinfunction "XTAL_1") (pintype "passive"))
      (node (ref "X2") (pin "1") (pintype "passive"))
    )
    (net (code "48") (name "Net-(U10-+IN)") (class "Default")
      (node (ref "R15") (pin "1") (pinfunction "1_1") (pintype "passive"))
      (node (ref "U10") (pin "1") (pinfunction "+IN_1") (pintype "passive"))
      (node (ref "U9") (pin "4") (pinfunction "B_4") (pintype "passive"))
      (node (ref "U9") (pin "6") (pinfunction "B_6") (pintype "passive"))
    )
    (net (code "49") (name "Net-(U12-+IN)") (class "Default")
      (node (ref "R26") (pin "2") (pintype "passive"))
      (node (ref "U12") (pin "1") (pinfunction "+IN_1") (pintype "passive"))
    )
    (net (code "50") (name "Net-(U12--IN)") (class "Default")
      (node (ref "C27") (pin "2") (pinfunction "2_2") (pintype "passive"))
      (node (ref "R28") (pin "2") (pinfunction "2_2") (pintype "passive"))
      (node (ref "R29") (pin "1") (pinfunction "1_1") (pintype "passive"))
      (node (ref "U12") (pin "3") (pinfunction "-IN_3") (pintype "passive"))
    )
    (net (code "51") (name "Net-(U13-BP)") (class "Default")
      (node (ref "C41") (pin "2") (pinfunction "2_2") (pintype "passive"))
      (node (ref "U13") (pin "4") (pinfunction "BP_4") (pintype "passive"))
    )
    (net (code "52") (name "Net-(X1-OSC2)") (class "Default")
      (node (ref "R1") (pin "1") (pinfunction "1_1") (pintype "passive"))
      (node (ref "X1") (pin "3") (pinfunction "OSC2_3") (pintype "passive"))
    )
    (net (code "53") (name "unconnected-(DLOAD-D--Pad2)") (class "Default")
      (node (ref "DLOAD") (pin "2") (pinfunction "D-_2") (pintype "passive"))
    )
    (net (code "54") (name "unconnected-(U1-NRST-Pad7)") (class "Default")
      (node (ref "U1") (pin "7") (pinfunction "NRST_7") (pintype "bidirectional"))
    )
    (net (code "55") (name "unconnected-(U1-PA0-WKUP-Pad14)") (class "Default")
      (node (ref "U1") (pin "14") (pinfunction "PA0-WKUP_14") (pintype "bidirectional"))
    )
    (net (code "56") (name "unconnected-(U1-PA4-Pad20)") (class "Default")
      (node (ref "U1") (pin "20") (pinfunction "PA4_20") (pintype "bidirectional"))
    )
    (net (code "57") (name "unconnected-(U1-PA5-Pad21)") (class "Default")
      (node (ref "U1") (pin "21") (pinfunction "PA5_21") (pintype "bidirectional"))
    )
    (net (code "58") (name "unconnected-(U1-PA6-Pad22)") (class "Default")
      (node (ref "U1") (pin "22") (pinfunction "PA6_22") (pintype "bidirectional"))
    )
    (net (code "59") (name "unconnected-(U1-PA7-Pad23)") (class "Default")
      (node (ref "U1") (pin "23") (pinfunction "PA7_23") (pintype "bidirectional"))
    )
    (net (code "60") (name "unconnected-(U1-PA8-Pad41)") (class "Default")
      (node (ref "U1") (pin "41") (pinfunction "PA8_41") (pintype "bidirectional"))
    )
    (net (code "61") (name "unconnected-(U1-PA9-Pad42)") (class "Default")
      (node (ref "U1") (pin "42") (pinfunction "PA9_42") (pintype "bidirectional"))
    )
    (net (code "62") (name "unconnected-(U1-PA10-Pad43)") (class "Default")
      (node (ref "U1") (pin "43") (pinfunction "PA10_43") (pintype "bidirectional"))
    )
    (net (code "63") (name "unconnected-(U1-PA11-Pad44)") (class "Default")
      (node (ref "U1") (pin "44") (pinfunction "PA11_44") (pintype "bidirectional"))
    )
    (net (code "64") (name "unconnected-(U1-PA12-Pad45)") (class "Default")
      (node (ref "U1") (pin "45") (pinfunction "PA12_45") (pintype "bidirectional"))
    )
    (net (code "65") (name "unconnected-(U1-PA15{slash}JTDI-Pad50)") (class "Default")
      (node (ref "U1") (pin "50") (pinfunction "PA15/JTDI_50") (pintype "bidirectional"))
    )
    (net (code "66") (name "unconnected-(U1-PB2{slash}BOOT1-Pad28)") (class "Default")
      (node (ref "U1") (pin "28") (pinfunction "PB2/BOOT1_28") (pintype "bidirectional"))
    )
    (net (code "67") (name "unconnected-(U1-PB3{slash}JTDO-Pad55)") (class "Default")
      (node (ref "U1") (pin "55") (pinfunction "PB3/JTDO_55") (pintype "bidirectional"))
    )
    (net (code "68") (name "unconnected-(U1-PB4{slash}JNTRST-Pad56)") (class "Default")
      (node (ref "U1") (pin "56") (pinfunction "PB4/JNTRST_56") (pintype "bidirectional"))
    )
    (net (code "69") (name "unconnected-(U1-PB5-Pad57)") (class "Default")
      (node (ref "U1") (pin "57") (pinfunction "PB5_57") (pintype "bidirectional"))
    )
    (net (code "70") (name "unconnected-(U1-PB7-Pad59)") (class "Default")
      (node (ref "U1") (pin "59") (pinfunction "PB7_59") (pintype "bidirectional"))
    )
    (net (code "71") (name "unconnected-(U1-PB8-Pad61)") (class "Default")
      (node (ref "U1") (pin "61") (pinfunction "PB8_61") (pintype "bidirectional"))
    )
    (net (code "72") (name "unconnected-(U1-PB9-Pad62)") (class "Default")
      (node (ref "U1") (pin "62") (pinfunction "PB9_62") (pintype "bidirectional"))
    )
    (net (code "73") (name "unconnected-(U1-PB14-Pad35)") (class "Default")
      (node (ref "U1") (pin "35") (pinfunction "PB14_35") (pintype "bidirectional"))
    )
    (net (code "74") (name "unconnected-(U1-PB15-Pad36)") (class "Default")
      (node (ref "U1") (pin "36") (pinfunction "PB15_36") (pintype "bidirectional"))
    )
    (net (code "75") (name "unconnected-(U1-PC0-Pad8)") (class "Default")
      (node (ref "U1") (pin "8") (pinfunction "PC0_8") (pintype "bidirectional"))
    )
    (net (code "76") (name "unconnected-(U1-PC1-Pad9)") (class "Default")
      (node (ref "U1") (pin "9") (pinfunction "PC1_9") (pintype "bidirectional"))
    )
    (net (code "77") (name "unconnected-(U1-PC2-Pad10)") (class "Default")
      (node (ref "U1") (pin "10") (pinfunction "PC2_10") (pintype "bidirectional"))
    )
    (net (code "78") (name "unconnected-(U1-PC3-Pad11)") (class "Default")
      (node (ref "U1") (pin "11") (pinfunction "PC3_11") (pintype "bidirectional"))
    )
    (net (code "79") (name "unconnected-(U1-PC4-Pad24)") (class "Default")
      (node (ref "U1") (pin "24") (pinfunction "PC4_24") (pintype "bidirectional"))
    )
    (net (code "80") (name "unconnected-(U1-PC5-Pad25)") (class "Default")
      (node (ref "U1") (pin "25") (pinfunction "PC5_25") (pintype "bidirectional"))
    )
    (net (code "81") (name "unconnected-(U1-PC6-Pad37)") (class "Default")
      (node (ref "U1") (pin "37") (pinfunction "PC6_37") (pintype "bidirectional"))
    )
    (net (code "82") (name "unconnected-(U1-PC7-Pad38)") (class "Default")
      (node (ref "U1") (pin "38") (pinfunction "PC7_38") (pintype "bidirectional"))
    )
    (net (code "83") (name "unconnected-(U1-PC8-Pad39)") (class "Default")
      (node (ref "U1") (pin "39") (pinfunction "PC8_39") (pintype "bidirectional"))
    )
    (net (code "84") (name "unconnected-(U1-PC9-Pad40)") (class "Default")
      (node (ref "U1") (pin "40") (pinfunction "PC9_40") (pintype "bidirectional"))
    )
    (net (code "85") (name "unconnected-(U1-PC10-Pad51)") (class "Default")
      (node (ref "U1") (pin "51") (pinfunction "PC10_51") (pintype "bidirectional"))
    )
    (net (code "86") (name "unconnected-(U1-PC11-Pad52)") (class "Default")
      (node (ref "U1") (pin "52") (pinfunction "PC11_52") (pintype "bidirectional"))
    )
    (net (code "87") (name "unconnected-(U1-PC12-Pad53)") (class "Default")
      (node (ref "U1") (pin "53") (pinfunction "PC12_53") (pintype "bidirectional"))
    )
    (net (code "88") (name "unconnected-(U1-PC15-OSC32_OUT-Pad4)") (class "Default")
      (node (ref "U1") (pin "4") (pinfunction "PC15-OSC32_OUT_4") (pintype "bidirectional"))
    )
    (net (code "89") (name "unconnected-(U1-PD2-Pad54)") (class "Default")
      (node (ref "U1") (pin "54") (pinfunction "PD2_54") (pintype "bidirectional"))
    )
    (net (code "90") (name "unconnected-(U1-VBAT-Pad1)") (class "Default")
      (node (ref "U1") (pin "1") (pinfunction "VBAT_1") (pintype "power_in"))
    )
    (net (code "91") (name "unconnected-(U4-EN-Pad2)") (class "Default")
      (node (ref "U4") (pin "2") (pinfunction "EN_2") (pintype "passive"))
    )
    (net (code "92") (name "unconnected-(U8-NC-Pad3)") (class "Default")
      (node (ref "U8") (pin "3") (pinfunction "NC_3") (pintype "passive"))
    )
    (net (code "93") (name "unconnected-(U8-NC-Pad4)") (class "Default")
      (node (ref "U8") (pin "4") (pinfunction "NC_4") (pintype "passive"))
    )
  )
)
